# USB_Interfaces.net
KiCad netlist of a schematic drawn in Altium Designer
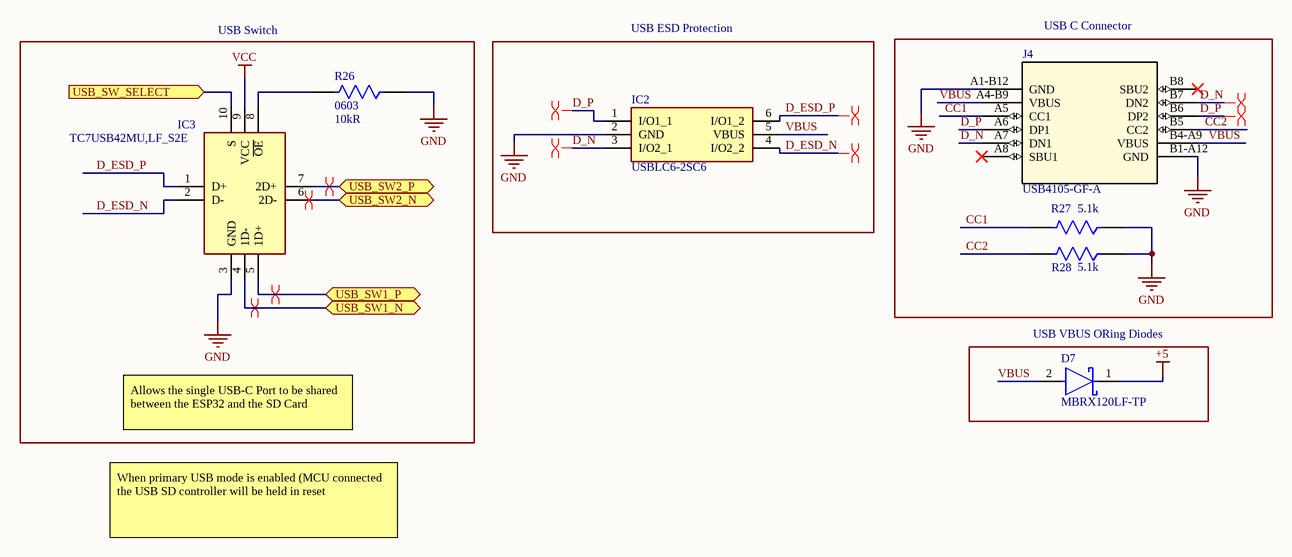
[diagram p0: USB_Interfaces.SchDoc]

(export (version "E")
  (design (tool "Eeschema 10.0.6"))
  (components
    (comp (ref "D7")
      (value "MBRX120LF-TP")
      (footprint "FP-SOD-123-IPC_A")
      (description "DIODE SCHOTTKY 20V 1A SOD123")
      (libsource (lib "Altium Content Vault") (part "1d6ec82d83fb6aee721767c19dac4b9"))
    )
    (comp (ref "IC2")
      (value "USBLC6-2SC6")
      (footprint "SOT95P280X145-6N")
      (description "Integrated Circuit")
      (fields (field (name "MOUSER PART NUMBER") "511-USBLC6-2SC6"))
      (libsource (lib "WiCAN_lib") (part "USBLC6-2SC6"))
    )
    (comp (ref "IC3")
      (value "TC7USB42MU,LF_S2E")
      (footprint "TC7USB42MULFS2E")
      (description "Integrated Circuit")
      (fields
        (field (name "MANUFACTURER_PART_NUMBER") "TC7USB42MU,LF(S2E")
        (field (name "MOUSER PART NUMBER") "757-TC7USB42MULFS2E")
      )
      (libsource (lib "WiCAN_lib") (part "TC7USB42MU,LF_S2E"))
    )
    (comp (ref "J4")
      (value "USB4105-GF-A")
      (footprint "USB4105_GCT")
      (description "No Description Available")
      (fields (field (name "COPYRIGHT") "Copyright (C) 2022 Ultra Librarian. All rights reserved."))
      (libsource (lib "WiCAN_lib") (part "USB4105-GF-A"))
    )
    (comp (ref "R26")
      (value "RMCF0603JG10K0")
      (footprint "FP-RMCF0603-MFG")
      (description "10kΩ ±5% 0.1W 0603 Thick Film Chip Resistor AEC-Q200 compliant")
      (fields
        (field (name "TOLERANCE") "5%")
        (field (name "CASE CODE (IMPERIAL)") "0603")
        (field (name "RESISTANCE") "10kR")
      )
      (libsource (lib "Altium Content Vault") (part "1029c3af85768c4190bb7ad29bc67b5"))
    )
    (comp (ref "R27")
      (value "AC0603FR-135K1L")
      (footprint "FP-AC0603-MFG")
      (description "RES 5.1KΩ 1.00% 0.1W 0603")
      (fields (field (name "RESISTOR") "5.1k"))
      (libsource (lib "Altium Content Vault") (part "1029c3af85768c4190bb7ad29bc67b5"))
    )
    (comp (ref "R28")
      (value "AC0603FR-135K1L")
      (footprint "FP-AC0603-MFG")
      (description "RES 5.1KΩ 1.00% 0.1W 0603")
      (fields (field (name "RESISTOR") "5.1k"))
      (libsource (lib "Altium Content Vault") (part "1029c3af85768c4190bb7ad29bc67b5"))
    )
  )
  (nets
    (net (code "1") (name "+5") (class "Default")
      (node (ref "D7") (pin "1") (pinfunction "C_1") (pintype "passive"))
    )
    (net (code "2") (name "/CC1") (class "Default")
      (node (ref "J4") (pin "A5") (pinfunction "CC1_A5") (pintype "bidirectional"))
      (node (ref "R27") (pin "2") (pinfunction "2_2") (pintype "passive"))
    )
    (net (code "3") (name "/CC2") (class "Default")
      (node (ref "J4") (pin "B5") (pinfunction "CC2_B5") (pintype "bidirectional"))
      (node (ref "R28") (pin "2") (pinfunction "2_2") (pintype "passive"))
    )
    (net (code "4") (name "/D_ESD_N") (class "Default")
      (node (ref "IC2") (pin "4") (pinfunction "I/O2_2_4") (pintype "passive"))
      (node (ref "IC3") (pin "2") (pinfunction "D-_2") (pintype "passive"))
    )
    (net (code "5") (name "/D_ESD_P") (class "Default")
      (node (ref "IC2") (pin "6") (pinfunction "I/O1_2_6") (pintype "passive"))
      (node (ref "IC3") (pin "1") (pinfunction "D+_1") (pintype "passive"))
    )
    (net (code "6") (name "/D_N") (class "Default")
      (node (ref "IC2") (pin "3") (pinfunction "I/O2_1_3") (pintype "passive"))
      (node (ref "J4") (pin "A7") (pinfunction "DN1_A7") (pintype "bidirectional"))
      (node (ref "J4") (pin "B7") (pinfunction "DN2_B7") (pintype "bidirectional"))
    )
    (net (code "7") (name "/D_P") (class "Default")
      (node (ref "IC2") (pin "1") (pinfunction "I/O1_1_1") (pintype "passive"))
      (node (ref "J4") (pin "A6") (pinfunction "DP1_A6") (pintype "bidirectional"))
      (node (ref "J4") (pin "B6") (pinfunction "DP2_B6") (pintype "bidirectional"))
    )
    (net (code "8") (name "/USB_SW1_N") (class "Default")
      (node (ref "IC3") (pin "4") (pinfunction "1D-_4") (pintype "passive"))
    )
    (net (code "9") (name "/USB_SW1_P") (class "Default")
      (node (ref "IC3") (pin "5") (pinfunction "1D+_5") (pintype "passive"))
    )
    (net (code "10") (name "/USB_SW2_N") (class "Default")
      (node (ref "IC3") (pin "6") (pinfunction "2D-_6") (pintype "passive"))
    )
    (net (code "11") (name "/USB_SW2_P") (class "Default")
      (node (ref "IC3") (pin "7") (pinfunction "2D+_7") (pintype "passive"))
    )
    (net (code "12") (name "/USB_SW_SELECT") (class "Default")
      (node (ref "IC3") (pin "10") (pinfunction "S_10") (pintype "passive"))
    )
    (net (code "13") (name "/VBUS") (class "Default")
      (node (ref "D7") (pin "2") (pinfunction "A_2") (pintype "passive"))
      (node (ref "IC2") (pin "5") (pinfunction "VBUS_5") (pintype "passive"))
      (node (ref "J4") (pin "A4-B9") (pinfunction "VBUS_A4-B9") (pintype "power_in"))
      (node (ref "J4") (pin "B4-A9") (pinfunction "VBUS_B4-A9") (pintype "power_in"))
    )
    (net (code "14") (name "GND") (class "Default")
      (node (ref "IC2") (pin "2") (pinfunction "GND_2") (pintype "passive"))
      (node (ref "IC3") (pin "3") (pinfunction "GND_3") (pintype "passive"))
      (node (ref "J4") (pin "A1-B12") (pinfunction "GND_A1-B12") (pintype "passive"))
      (node (ref "J4") (pin "B1-A12") (pinfunction "GND_B1-A12") (pintype "passive"))
      (node (ref "R26") (pin "1") (pinfunction "1_1") (pintype "passive"))
      (node (ref "R27") (pin "1") (pinfunction "1_1") (pintype "passive"))
      (node (ref "R28") (pin "1") (pinfunction "1_1") (pintype "passive"))
    )
    (net (code "15") (name "Net-(IC3-~{OE})") (class "Default")
      (node (ref "IC3") (pin "8") (pinfunction "~{OE}_8") (pintype "passive"))
      (node (ref "R26") (pin "2") (pinfunction "2_2") (pintype "passive"))
    )
    (net (code "16") (name "VCC") (class "Default")
      (node (ref "IC3") (pin "9") (pinfunction "VCC_9") (pintype "passive"))
    )
    (net (code "17") (name "unconnected-(J4-SBU1-PadA8)") (class "Default")
      (node (ref "J4") (pin "A8") (pinfunction "SBU1_A8") (pintype "bidirectional+no_connect"))
    )
    (net (code "18") (name "unconnected-(J4-SBU2-PadB8)") (class "Default")
      (node (ref "J4") (pin "B8") (pinfunction "SBU2_B8") (pintype "bidirectional+no_connect"))
    )
  )
)
